# cond_sinais.net
KiCad netlist of a schematic drawn in Altium Designer
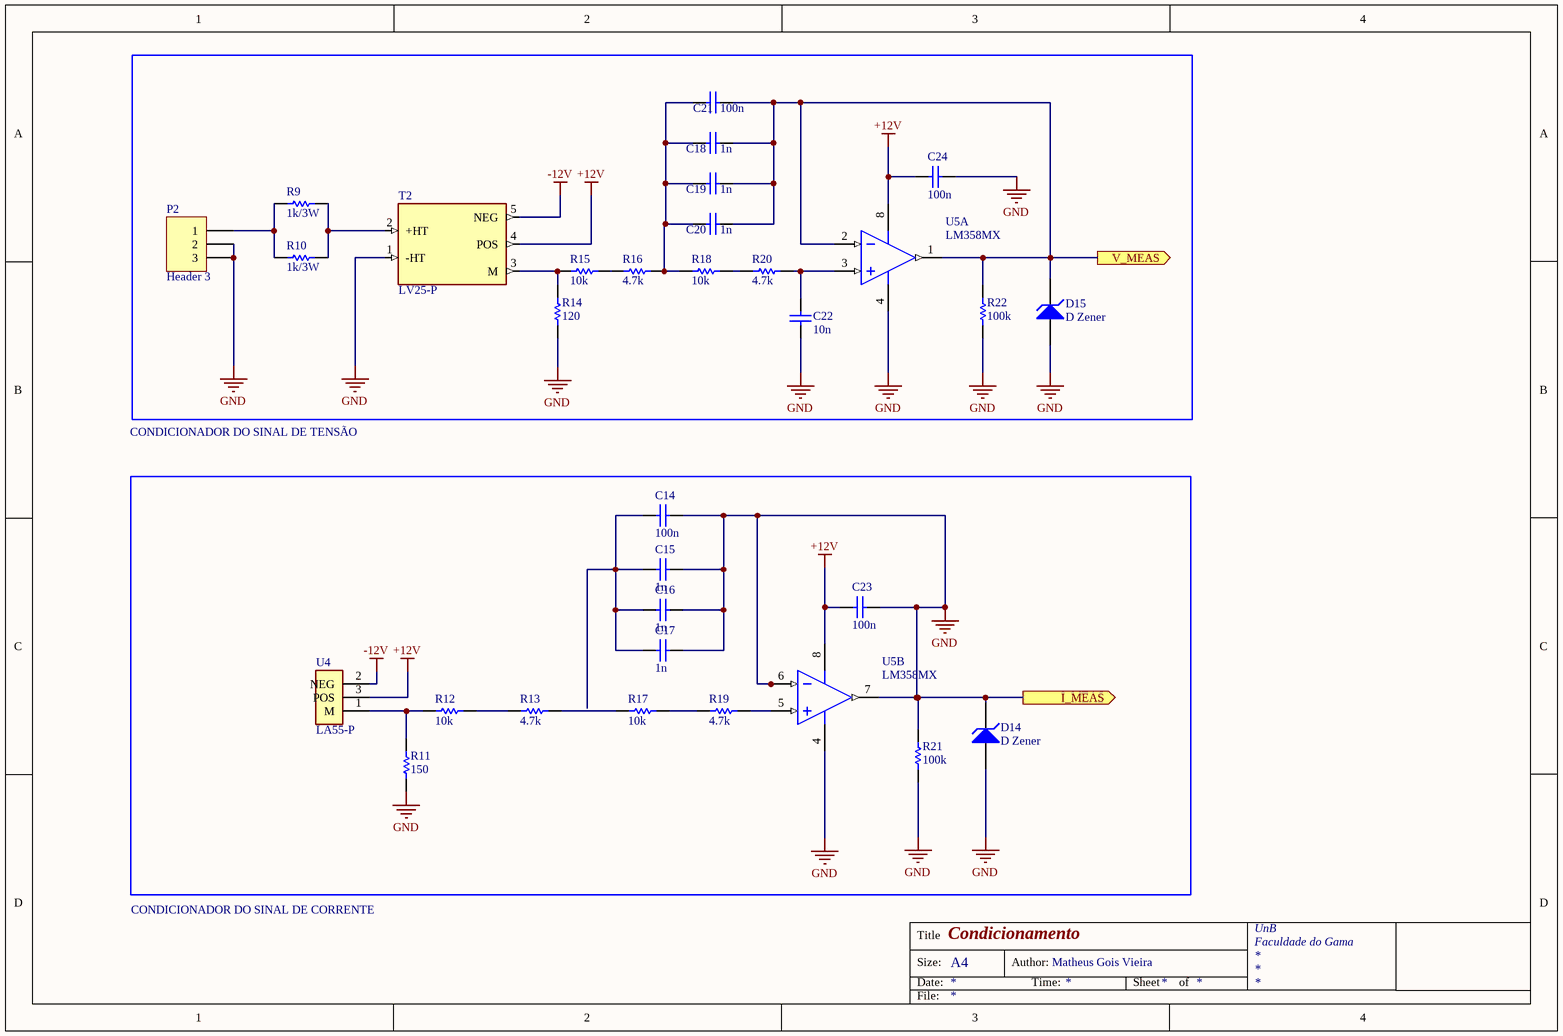
[diagram p0: cond_sinais.SchDoc]

(export (version "E")
  (design (tool "Eeschema 10.0.6"))
  (components
    (comp (ref "C14")
      (value "100n")
      (footprint "C0603[0201]")
      (description "CAP CER 10000PF 50V X7R 0603")
      (fields (field (name "MANUFACTURER PART NUMBER") "C0603C103K5RACTU") (field (name "TOLERANCE") "10%"))
      (libsource (lib "Basic Library") (part "C"))
    )
    (comp (ref "C15")
      (value "1n")
      (footprint "C0603[0201]")
      (description "Cap Ceramic 0.001uF 50V X7R 10% SMD 0603 125C T/R")
      (fields (field (name "MANUFACTURER PART NUMBER") "C0603C102K5RACTU") (field (name "TOLERANCE") "10%"))
      (libsource (lib "Basic Library") (part "C"))
    )
    (comp (ref "C16")
      (value "1n")
      (footprint "C0603[0201]")
      (description "Cap Ceramic 0.001uF 50V X7R 10% SMD 0603 125C T/R")
      (fields (field (name "MANUFACTURER PART NUMBER") "C0603C102K5RACTU") (field (name "TOLERANCE") "10%"))
      (libsource (lib "Basic Library") (part "C"))
    )
    (comp (ref "C17")
      (value "1n")
      (footprint "C0603[0201]")
      (description "Cap Ceramic 0.001uF 50V X7R 10% SMD 0603 125C T/R")
      (fields (field (name "MANUFACTURER PART NUMBER") "C0603C102K5RACTU") (field (name "TOLERANCE") "10%"))
      (libsource (lib "Basic Library") (part "C"))
    )
    (comp (ref "C18")
      (value "1n")
      (footprint "C0603[0201]")
      (description "Cap Ceramic 0.001uF 50V X7R 10% SMD 0603 125C T/R")
      (fields (field (name "MANUFACTURER PART NUMBER") "C0603C102K5RACTU") (field (name "TOLERANCE") "10%"))
      (libsource (lib "Basic Library") (part "C"))
    )
    (comp (ref "C19")
      (value "1n")
      (footprint "C0603[0201]")
      (description "Cap Ceramic 0.001uF 50V X7R 10% SMD 0603 125C T/R")
      (fields (field (name "MANUFACTURER PART NUMBER") "C0603C102K5RACTU") (field (name "TOLERANCE") "10%"))
      (libsource (lib "Basic Library") (part "C"))
    )
    (comp (ref "C20")
      (value "1n")
      (footprint "C0603[0201]")
      (description "Cap Ceramic 0.001uF 50V X7R 10% SMD 0603 125C T/R")
      (fields (field (name "MANUFACTURER PART NUMBER") "C0603C102K5RACTU") (field (name "TOLERANCE") "10%"))
      (libsource (lib "Basic Library") (part "C"))
    )
    (comp (ref "C21")
      (value "100n")
      (footprint "C0603[0201]")
      (description "CAP CER 10000PF 50V X7R 0603")
      (fields (field (name "MANUFACTURER PART NUMBER") "C0603C103K5RACTU") (field (name "TOLERANCE") "10%"))
      (libsource (lib "Basic Library") (part "C"))
    )
    (comp (ref "C22")
      (value "10n")
      (footprint "C0603[0201]")
      (description "CAP CER 10000PF 50V X7R 0603")
      (fields (field (name "MANUFACTURER PART NUMBER") "C0603C103K5RACTU") (field (name "TOLERANCE") "10%"))
      (libsource (lib "Basic Library") (part "C"))
    )
    (comp (ref "C23")
      (value "100n")
      (footprint "C0603[0201]")
      (description "贴片陶瓷电容 0.1uF ±10% 50V X7R 0603")
      (fields (field (name "MANUFACTURER PART NUMBER") "C0603C104K5RACTU") (field (name "TOLERANCE") "10%"))
      (libsource (lib "Basic Library") (part "C"))
    )
    (comp (ref "C24")
      (value "100n")
      (footprint "C0603[0201]")
      (description "贴片陶瓷电容 0.1uF ±10% 50V X7R 0603")
      (fields (field (name "MANUFACTURER PART NUMBER") "C0603C104K5RACTU") (field (name "TOLERANCE") "10%"))
      (libsource (lib "Basic Library") (part "C"))
    )
    (comp (ref "D14")
      (value "D Zener")
      (footprint "DIODE-SIGNAL")
      (description "Diode Zener Single 9.1V 5% 500mW 2-Pin(1+Tab) Power Mite T/R")
      (fields (field (name "MANUFACTURER PART NUMBER") "1PMT5924BT1G") (field (name "TOLERANCE") "5%"))
      (libsource (lib "Basic Library") (part "D Zener"))
    )
    (comp (ref "D15")
      (value "D Zener")
      (footprint "DIODE-SIGNAL")
      (description "Diode Zener Single 9.1V 5% 500mW 2-Pin(1+Tab) Power Mite T/R")
      (fields (field (name "MANUFACTURER PART NUMBER") "1PMT5924BT1G") (field (name "TOLERANCE") "5%"))
      (libsource (lib "Basic Library") (part "D Zener"))
    )
    (comp (ref "P2")
      (value "Header 3")
      (footprint "HDR1X3")
      (description "Header, 3-Pin")
      (fields (field (name "PUBLISHER") "Altium Limited"))
      (libsource (lib "Miscellaneous Connectors") (part "Header 3"))
    )
    (comp (ref "R9")
      (value "1k/3W")
      (footprint "R1005[0402]")
      (description "Res Thick Film 2512 1K Ohm 5% 3W ±100ppm/C Pad SMD T/R")
      (fields (field (name "MANUFACTURER PART NUMBER") "35221K0JT") (field (name "TOLERANCE") "5%"))
      (libsource (lib "Basic Library") (part "R"))
    )
    (comp (ref "R10")
      (value "1k/3W")
      (footprint "R1005[0402]")
      (description "Res Thick Film 2512 1K Ohm 5% 3W ±100ppm/C Pad SMD T/R")
      (fields (field (name "MANUFACTURER PART NUMBER") "35221K0JT") (field (name "TOLERANCE") "5%"))
      (libsource (lib "Basic Library") (part "R"))
    )
    (comp (ref "R11")
      (value "150")
      (footprint "R1005[0402]")
      (description "贴片电阻 150Ω ±1% 1/4W ±100ppm/℃ 1206")
      (fields (field (name "MANUFACTURER PART NUMBER") "ERJ-8ENF1500V") (field (name "TOLERANCE") "1%"))
      (libsource (lib "Basic Library") (part "R"))
    )
    (comp (ref "R12")
      (value "10k")
      (footprint "R1608[0603]")
      (description "Res, 10K, 0.01%, 0.25W, 1206, Metal Foil")
      (fields (field (name "MANUFACTURER PART NUMBER") "Y163010K0000T9R") (field (name "TOLERANCE") "0.01%"))
      (libsource (lib "Basic Library") (part "R"))
    )
    (comp (ref "R13")
      (value "4.7k")
      (footprint "R1005[0402]")
      (description "Res Thick Film 1206 4.7K Ohm 5% 1/4W ±200ppm/°C Molded SMD Punched Carrier T/R")
      (fields (field (name "MANUFACTURER PART NUMBER") "ERJ-8GEYJ472V") (field (name "TOLERANCE") "5%"))
      (libsource (lib "Basic Library") (part "R"))
    )
    (comp (ref "R14")
      (value "120")
      (footprint "R1005[0402]")
      (description "Resistor Thick Film 1206 120 Ohm 5% 1/4W 200ppm/C Molded SMD Punched Carrier T/R")
      (fields (field (name "MANUFACTURER PART NUMBER") "ERJ-8GEYJ121V") (field (name "TOLERANCE") "5%"))
      (libsource (lib "Basic Library") (part "R"))
    )
    (comp (ref "R15")
      (value "10k")
      (footprint "R1608[0603]")
      (description "Res, 10K, 0.01%, 0.25W, 1206, Metal Foil")
      (fields (field (name "MANUFACTURER PART NUMBER") "Y163010K0000T9R") (field (name "TOLERANCE") "0.01%"))
      (libsource (lib "Basic Library") (part "R"))
    )
    (comp (ref "R16")
      (value "4.7k")
      (footprint "R1005[0402]")
      (description "Res Thick Film 1206 4.7K Ohm 5% 1/4W ±200ppm/°C Molded SMD Punched Carrier T/R")
      (fields (field (name "MANUFACTURER PART NUMBER") "ERJ-8GEYJ472V") (field (name "TOLERANCE") "5%"))
      (libsource (lib "Basic Library") (part "R"))
    )
    (comp (ref "R17")
      (value "10k")
      (footprint "R1005[0402]")
      (description "Res, 10K, 0.01%, 0.25W, 1206, Metal Foil")
      (fields (field (name "MANUFACTURER PART NUMBER") "Y163010K0000T9R") (field (name "TOLERANCE") "0.01%"))
      (libsource (lib "Basic Library") (part "R"))
    )
    (comp (ref "R18")
      (value "10k")
      (footprint "R1005[0402]")
      (description "Res, 10K, 0.01%, 0.25W, 1206, Metal Foil")
      (fields (field (name "MANUFACTURER PART NUMBER") "Y163010K0000T9R") (field (name "TOLERANCE") "0.01%"))
      (libsource (lib "Basic Library") (part "R"))
    )
    (comp (ref "R19")
      (value "4.7k")
      (footprint "R1005[0402]")
      (description "Res Thick Film 1206 4.7K Ohm 5% 1/4W ±200ppm/°C Molded SMD Punched Carrier T/R")
      (fields (field (name "MANUFACTURER PART NUMBER") "ERJ-8GEYJ472V") (field (name "TOLERANCE") "5%"))
      (libsource (lib "Basic Library") (part "R"))
    )
    (comp (ref "R20")
      (value "4.7k")
      (footprint "R1005[0402]")
      (description "Res Thick Film 1206 4.7K Ohm 5% 1/4W ±200ppm/°C Molded SMD Punched Carrier T/R")
      (fields (field (name "MANUFACTURER PART NUMBER") "ERJ-8GEYJ472V") (field (name "TOLERANCE") "5%"))
      (libsource (lib "Basic Library") (part "R"))
    )
    (comp (ref "R21")
      (value "100k")
      (footprint "R1005[0402]")
      (description "贴片电阻 100KΩ ±1% 1/4W ±100ppm/℃ 1206")
      (fields (field (name "MANUFACTURER PART NUMBER") "ERJ-8ENF1003V") (field (name "TOLERANCE") "1%"))
      (libsource (lib "Basic Library") (part "R"))
    )
    (comp (ref "R22")
      (value "100k")
      (footprint "R1005[0402]")
      (description "贴片电阻 100KΩ ±1% 1/4W ±100ppm/℃ 1206")
      (fields (field (name "MANUFACTURER PART NUMBER") "ERJ-8ENF1003V") (field (name "TOLERANCE") "1%"))
      (libsource (lib "Basic Library") (part "R"))
    )
    (comp (ref "T2")
      (value "LV25-P")
      (footprint "XDCR_LV25-P")
      (description "Hall Effect Voltage Transducer")
      (fields (field (name "DIGI-KEY_PART_NUMBER") "398-1019-ND") (field (name "MF") "LEM USA Inc."))
      (libsource (lib "LV25-P") (part "LV25-P"))
    )
    (comp (ref "U4")
      (value "LA55-P")
      (footprint "XDCR_LA55-P")
      (description "Current Sensor 50A 1 Channel Hall Effect, Closed Loop Bidirectional Module, Single Pass Through")
      (fields (field (name "MP") "LA 55-P") (field (name "MF") "LEM USA"))
      (libsource (lib "LA55-P") (part "LA55-P"))
    )
    (comp (ref "U5")
      (value "LM358MX")
      (footprint "M08A_N")
      (description "LM358 Series 7 mV Input Offset Dual Operational Amplifier - SOIC-8")
      (fields (field (name "MANUFACTURER") "National Semiconductor"))
      (libsource (lib "National Semiconductor Amplifier") (part "LM358MX"))
    )
  )
  (nets
    (net (code "1") (name "+12V") (class "Default")
      (node (ref "C23") (pin "2") (pinfunction "2_2") (pintype "passive"))
      (node (ref "C24") (pin "2") (pinfunction "2_2") (pintype "passive"))
      (node (ref "T2") (pin "4") (pinfunction "POS_4") (pintype "output"))
      (node (ref "U4") (pin "3") (pinfunction "POS_3") (pintype "power_in"))
      (node (ref "U5") (pin "8") (pinfunction "V+_8") (pintype "power_in"))
    )
    (net (code "2") (name "-12V") (class "Default")
      (node (ref "T2") (pin "5") (pinfunction "NEG_5") (pintype "output"))
      (node (ref "U4") (pin "2") (pinfunction "NEG_2") (pintype "power_in"))
    )
    (net (code "3") (name "/V_MEAS") (class "Default")
      (node (ref "C18") (pin "2") (pinfunction "2_2") (pintype "passive"))
      (node (ref "C19") (pin "2") (pinfunction "2_2") (pintype "passive"))
      (node (ref "C20") (pin "2") (pinfunction "2_2") (pintype "passive"))
      (node (ref "C21") (pin "2") (pinfunction "2_2") (pintype "passive"))
      (node (ref "D15") (pin "2") (pinfunction "K_2") (pintype "passive"))
      (node (ref "R22") (pin "2") (pinfunction "2_2") (pintype "passive"))
      (node (ref "U5") (pin "1") (pinfunction "OUTA_1") (pintype "output"))
      (node (ref "U5") (pin "2") (pinfunction "INA-_2") (pintype "input"))
    )
    (net (code "4") (name "GND") (class "Default")
      (node (ref "C14") (pin "2") (pinfunction "2_2") (pintype "passive"))
      (node (ref "C15") (pin "2") (pinfunction "2_2") (pintype "passive"))
      (node (ref "C16") (pin "2") (pinfunction "2_2") (pintype "passive"))
      (node (ref "C17") (pin "2") (pinfunction "2_2") (pintype "passive"))
      (node (ref "C22") (pin "1") (pinfunction "1_1") (pintype "passive"))
      (node (ref "C23") (pin "1") (pinfunction "1_1") (pintype "passive"))
      (node (ref "C24") (pin "1") (pinfunction "1_1") (pintype "passive"))
      (node (ref "D14") (pin "1") (pinfunction "A_1") (pintype "passive"))
      (node (ref "D14") (pin "2") (pinfunction "K_2") (pintype "passive"))
      (node (ref "D15") (pin "1") (pinfunction "A_1") (pintype "passive"))
      (node (ref "P2") (pin "2") (pinfunction "2_2") (pintype "passive"))
      (node (ref "P2") (pin "3") (pinfunction "3_3") (pintype "passive"))
      (node (ref "R11") (pin "1") (pinfunction "1_1") (pintype "passive"))
      (node (ref "R14") (pin "1") (pinfunction "1_1") (pintype "passive"))
      (node (ref "R21") (pin "1") (pinfunction "1_1") (pintype "passive"))
      (node (ref "R21") (pin "2") (pinfunction "2_2") (pintype "passive"))
      (node (ref "R22") (pin "1") (pinfunction "1_1") (pintype "passive"))
      (node (ref "T2") (pin "1") (pinfunction "-HT_1") (pintype "input"))
      (node (ref "U5") (pin "4") (pinfunction "GND_4") (pintype "power_in"))
      (node (ref "U5") (pin "6") (pinfunction "INB-_6") (pintype "input"))
      (node (ref "U5") (pin "7") (pinfunction "OUTB_7") (pintype "output"))
    )
    (net (code "5") (name "Net-(C14-Pad1)") (class "Default")
      (node (ref "C14") (pin "1") (pinfunction "1_1") (pintype "passive"))
      (node (ref "C15") (pin "1") (pinfunction "1_1") (pintype "passive"))
      (node (ref "C16") (pin "1") (pinfunction "1_1") (pintype "passive"))
      (node (ref "C17") (pin "1") (pinfunction "1_1") (pintype "passive"))
    )
    (net (code "6") (name "Net-(C18-Pad1)") (class "Default")
      (node (ref "C18") (pin "1") (pinfunction "1_1") (pintype "passive"))
      (node (ref "C19") (pin "1") (pinfunction "1_1") (pintype "passive"))
      (node (ref "C20") (pin "1") (pinfunction "1_1") (pintype "passive"))
      (node (ref "C21") (pin "1") (pinfunction "1_1") (pintype "passive"))
      (node (ref "R16") (pin "2") (pinfunction "2_2") (pintype "passive"))
      (node (ref "R18") (pin "1") (pinfunction "1_1") (pintype "passive"))
    )
    (net (code "7") (name "Net-(P2-Pad1)") (class "Default")
      (node (ref "P2") (pin "1") (pinfunction "1_1") (pintype "passive"))
      (node (ref "R10") (pin "1") (pinfunction "1_1") (pintype "passive"))
      (node (ref "R9") (pin "1") (pinfunction "1_1") (pintype "passive"))
    )
    (net (code "8") (name "Net-(R12-Pad2)") (class "Default")
      (node (ref "R12") (pin "2") (pinfunction "2_2") (pintype "passive"))
      (node (ref "R13") (pin "1") (pinfunction "1_1") (pintype "passive"))
    )
    (net (code "9") (name "Net-(R13-Pad2)") (class "Default")
      (node (ref "R13") (pin "2") (pinfunction "2_2") (pintype "passive"))
      (node (ref "R17") (pin "1") (pinfunction "1_1") (pintype "passive"))
    )
    (net (code "10") (name "Net-(R15-Pad2)") (class "Default")
      (node (ref "R15") (pin "2") (pinfunction "2_2") (pintype "passive"))
      (node (ref "R16") (pin "1") (pinfunction "1_1") (pintype "passive"))
    )
    (net (code "11") (name "Net-(R17-Pad2)") (class "Default")
      (node (ref "R17") (pin "2") (pinfunction "2_2") (pintype "passive"))
      (node (ref "R19") (pin "1") (pinfunction "1_1") (pintype "passive"))
    )
    (net (code "12") (name "Net-(R18-Pad2)") (class "Default")
      (node (ref "R18") (pin "2") (pinfunction "2_2") (pintype "passive"))
      (node (ref "R20") (pin "1") (pinfunction "1_1") (pintype "passive"))
    )
    (net (code "13") (name "Net-(T2-+HT)") (class "Default")
      (node (ref "R10") (pin "2") (pinfunction "2_2") (pintype "passive"))
      (node (ref "R9") (pin "2") (pinfunction "2_2") (pintype "passive"))
      (node (ref "T2") (pin "2") (pinfunction "+HT_2") (pintype "input"))
    )
    (net (code "14") (name "Net-(T2-M)") (class "Default")
      (node (ref "R14") (pin "2") (pinfunction "2_2") (pintype "passive"))
      (node (ref "R15") (pin "1") (pinfunction "1_1") (pintype "passive"))
      (node (ref "T2") (pin "3") (pinfunction "M_3") (pintype "output"))
    )
    (net (code "15") (name "Net-(U4-M)") (class "Default")
      (node (ref "R11") (pin "2") (pinfunction "2_2") (pintype "passive"))
      (node (ref "R12") (pin "1") (pinfunction "1_1") (pintype "passive"))
      (node (ref "U4") (pin "1") (pinfunction "M_1") (pintype "power_in"))
    )
    (net (code "16") (name "Net-(U5A-INA+)") (class "Default")
      (node (ref "C22") (pin "2") (pinfunction "2_2") (pintype "passive"))
      (node (ref "R20") (pin "2") (pinfunction "2_2") (pintype "passive"))
      (node (ref "U5") (pin "3") (pinfunction "INA+_3") (pintype "input"))
    )
    (net (code "17") (name "Net-(U5B-INB+)") (class "Default")
      (node (ref "R19") (pin "2") (pinfunction "2_2") (pintype "passive"))
      (node (ref "U5") (pin "5") (pinfunction "INB+_5") (pintype "input"))
    )
  )
)
